# OUTPUT.net
KiCad netlist of a schematic drawn in Altium Designer
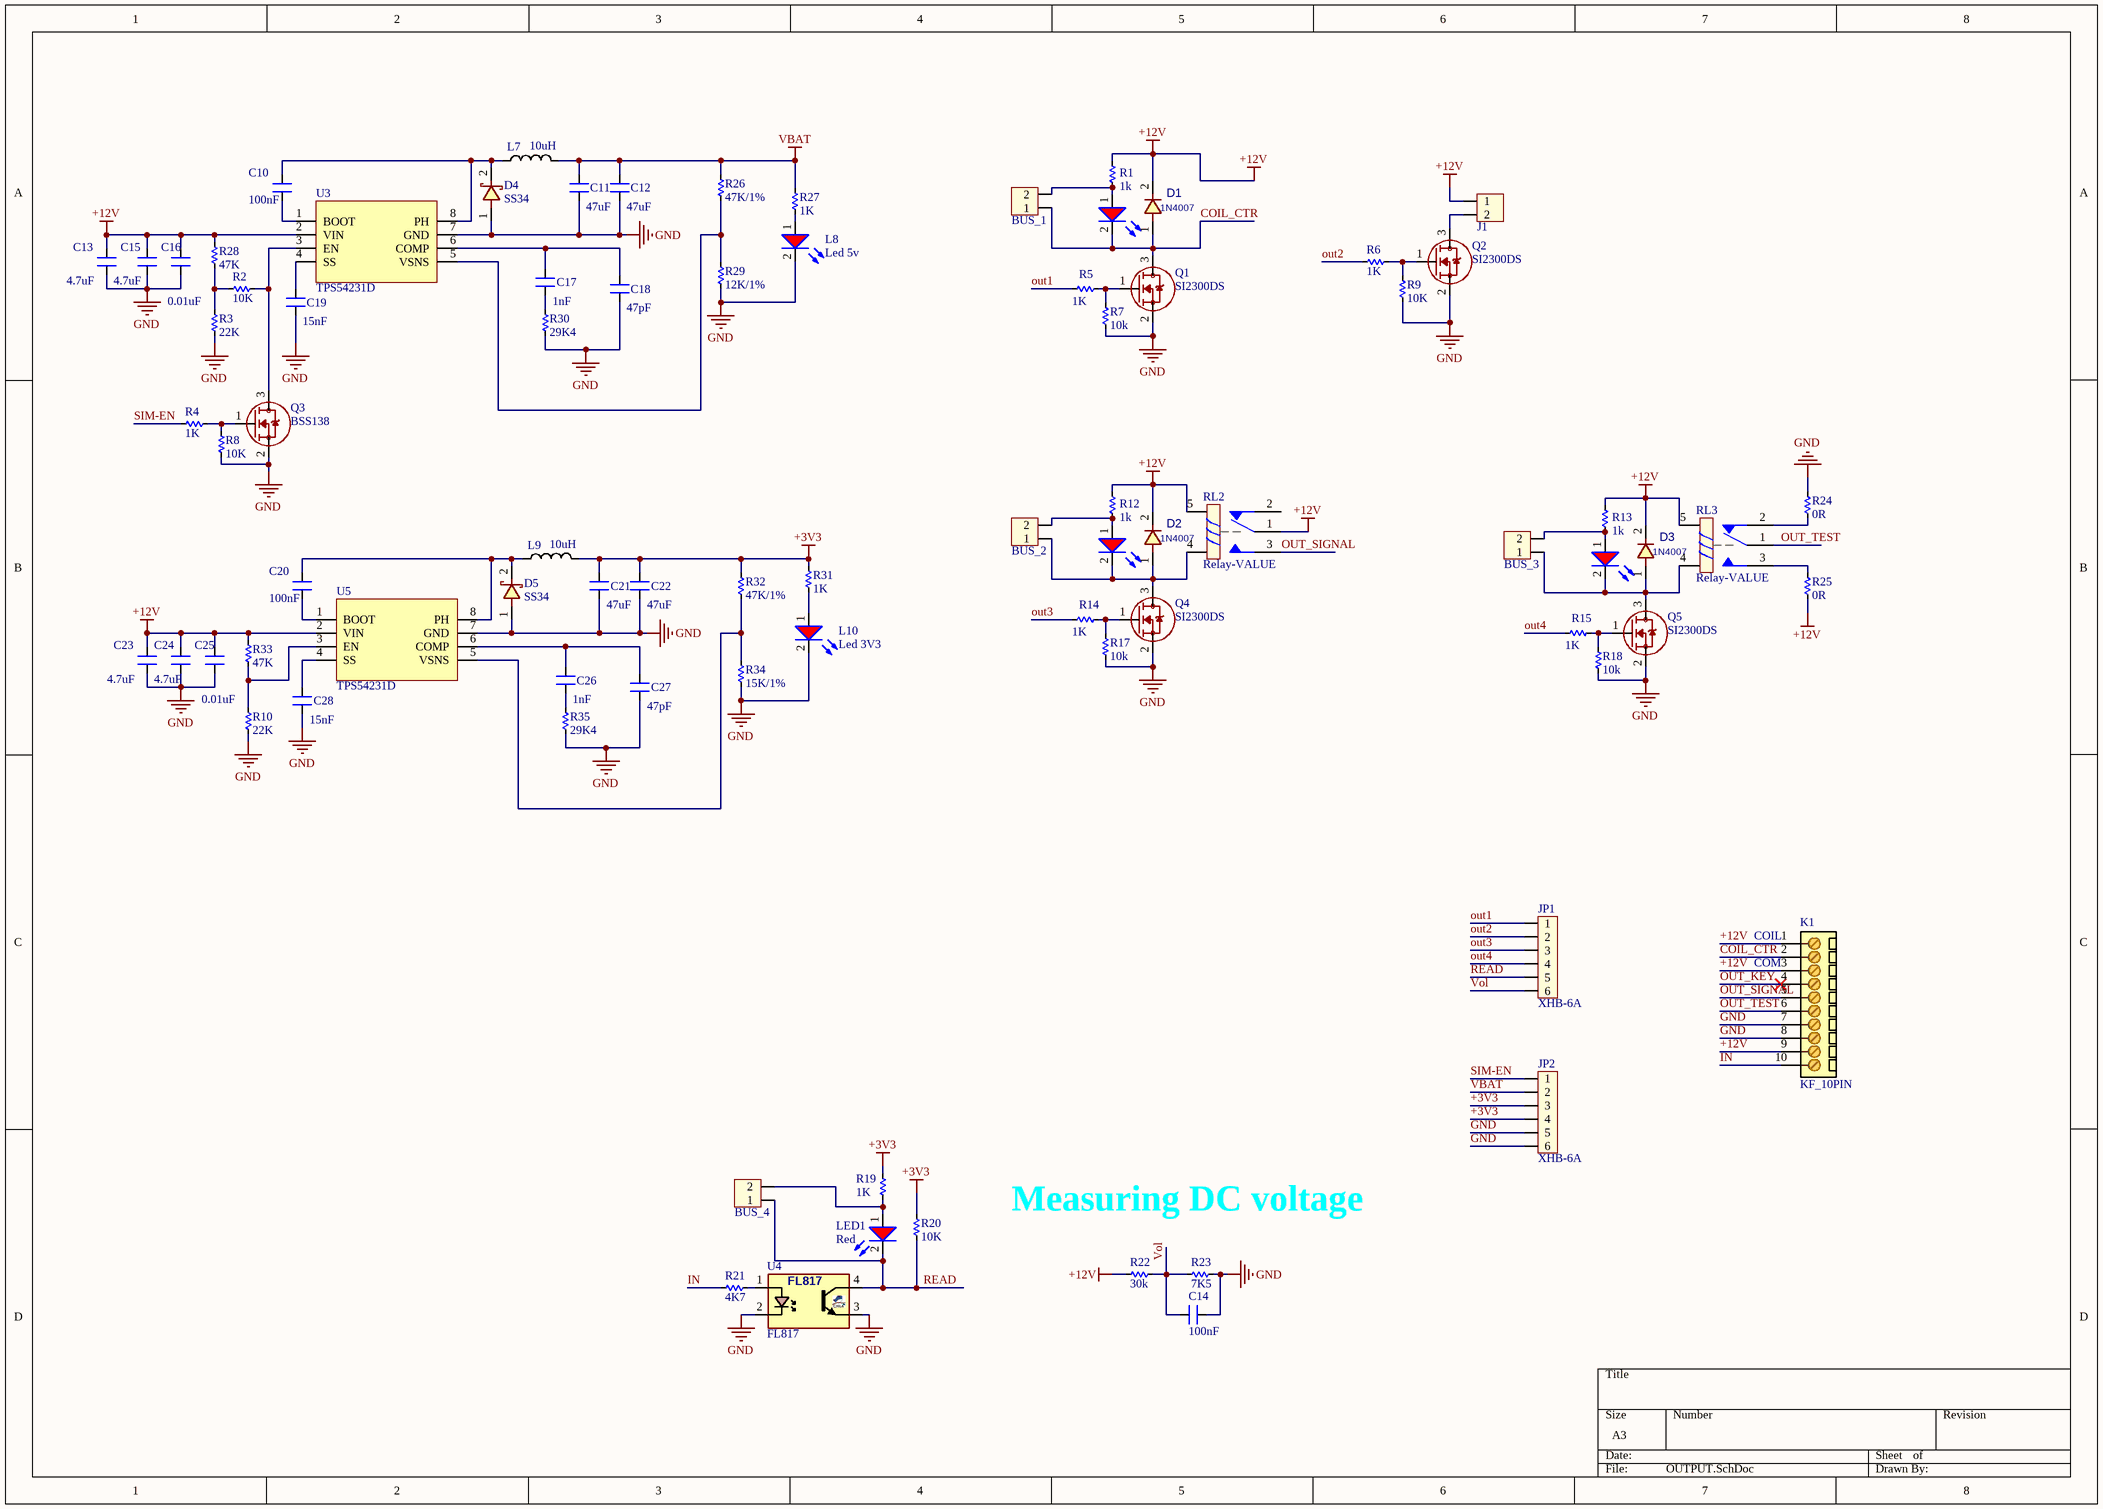
[diagram p0: OUTPUT.SchDoc]

(export (version "E")
  (design (tool "Eeschema 10.0.6"))
  (components
    (comp (ref "BUS_1")
      (value "BUS_2PIN")
      (footprint "CON2")
      (description "Connector 2")
      (libsource (lib "Tuấn Anh") (part "CON2"))
    )
    (comp (ref "BUS_2")
      (value "BUS_2PIN")
      (footprint "CON2")
      (description "Connector 2")
      (libsource (lib "Tuấn Anh") (part "CON2"))
    )
    (comp (ref "BUS_3")
      (value "BUS_2PIN")
      (footprint "CON2")
      (description "Connector 2")
      (libsource (lib "Tuấn Anh") (part "CON2"))
    )
    (comp (ref "BUS_4")
      (value "BUS_2PIN")
      (footprint "CON2")
      (description "Connector 2")
      (libsource (lib "Tuấn Anh") (part "CON2"))
    )
    (comp (ref "C10")
      (value "100nF")
      (footprint "CAP-0603")
      (description "Cap np W0.3")
      (fields (field (name "COPYRIGHT") "VanDungEvn"))
      (libsource (lib "tuananh_smd") (part "CAP CERAMIC"))
    )
    (comp (ref "C11")
      (value "47uF")
      (footprint "Cap-0805")
      (description "Cap np W0.3")
      (fields (field (name "COPYRIGHT") "VanDungEvn"))
      (libsource (lib "tuananh_smd") (part "CAP CERAMIC"))
    )
    (comp (ref "C12")
      (value "47uF")
      (footprint "Cap-0805")
      (description "Cap np W0.3")
      (fields (field (name "COPYRIGHT") "VanDungEvn"))
      (libsource (lib "tuananh_smd") (part "CAP CERAMIC"))
    )
    (comp (ref "C13")
      (value "4.7uF")
      (footprint "Cap-0805")
      (description "Cap np W0.3")
      (fields (field (name "COPYRIGHT") "VanDungEvn"))
      (libsource (lib "tuananh_smd") (part "CAP CERAMIC"))
    )
    (comp (ref "C14")
      (value "100nF")
      (footprint "CAP-0603")
      (description "Cap np W0.3")
      (fields (field (name "COPYRIGHT") "VanDungEvn"))
      (libsource (lib "tuananh_smd") (part "CAP CERAMIC"))
    )
    (comp (ref "C15")
      (value "4.7uF")
      (footprint "Cap-0805")
      (description "Cap np W0.3")
      (fields (field (name "COPYRIGHT") "VanDungEvn"))
      (libsource (lib "tuananh_smd") (part "CAP CERAMIC"))
    )
    (comp (ref "C16")
      (value "0.01uF")
      (footprint "CAP-0603")
      (description "Cap np W0.3")
      (fields (field (name "COPYRIGHT") "VanDungEvn"))
      (libsource (lib "tuananh_smd") (part "CAP CERAMIC"))
    )
    (comp (ref "C17")
      (value "1nF")
      (footprint "CAP-0603")
      (description "Cap np W0.3")
      (fields (field (name "COPYRIGHT") "VanDungEvn"))
      (libsource (lib "tuananh_smd") (part "CAP CERAMIC"))
    )
    (comp (ref "C18")
      (value "47pF")
      (footprint "CAP-0603")
      (description "Cap np W0.3")
      (fields (field (name "COPYRIGHT") "VanDungEvn"))
      (libsource (lib "tuananh_smd") (part "CAP CERAMIC"))
    )
    (comp (ref "C19")
      (value "15nF")
      (footprint "CAP-0603")
      (description "Cap np W0.3")
      (fields (field (name "COPYRIGHT") "VanDungEvn"))
      (libsource (lib "tuananh_smd") (part "CAP CERAMIC"))
    )
    (comp (ref "C20")
      (value "100nF")
      (footprint "CAP-0603")
      (description "Cap np W0.3")
      (fields (field (name "COPYRIGHT") "VanDungEvn"))
      (libsource (lib "tuananh_smd") (part "CAP CERAMIC"))
    )
    (comp (ref "C21")
      (value "47uF")
      (footprint "Cap-0805")
      (description "Cap np W0.3")
      (fields (field (name "COPYRIGHT") "VanDungEvn"))
      (libsource (lib "tuananh_smd") (part "CAP CERAMIC"))
    )
    (comp (ref "C22")
      (value "47uF")
      (footprint "Cap-0805")
      (description "Cap np W0.3")
      (fields (field (name "COPYRIGHT") "VanDungEvn"))
      (libsource (lib "tuananh_smd") (part "CAP CERAMIC"))
    )
    (comp (ref "C23")
      (value "4.7uF")
      (footprint "Cap-0805")
      (description "Cap np W0.3")
      (fields (field (name "COPYRIGHT") "VanDungEvn"))
      (libsource (lib "tuananh_smd") (part "CAP CERAMIC"))
    )
    (comp (ref "C24")
      (value "4.7uF")
      (footprint "Cap-0805")
      (description "Cap np W0.3")
      (fields (field (name "COPYRIGHT") "VanDungEvn"))
      (libsource (lib "tuananh_smd") (part "CAP CERAMIC"))
    )
    (comp (ref "C25")
      (value "0.01uF")
      (footprint "CAP-0603")
      (description "Cap np W0.3")
      (fields (field (name "COPYRIGHT") "VanDungEvn"))
      (libsource (lib "tuananh_smd") (part "CAP CERAMIC"))
    )
    (comp (ref "C26")
      (value "1nF")
      (footprint "CAP-0603")
      (description "Cap np W0.3")
      (fields (field (name "COPYRIGHT") "VanDungEvn"))
      (libsource (lib "tuananh_smd") (part "CAP CERAMIC"))
    )
    (comp (ref "C27")
      (value "47pF")
      (footprint "CAP-0603")
      (description "Cap np W0.3")
      (fields (field (name "COPYRIGHT") "VanDungEvn"))
      (libsource (lib "tuananh_smd") (part "CAP CERAMIC"))
    )
    (comp (ref "C28")
      (value "15nF")
      (footprint "CAP-0603")
      (description "Cap np W0.3")
      (fields (field (name "COPYRIGHT") "VanDungEvn"))
      (libsource (lib "tuananh_smd") (part "CAP CERAMIC"))
    )
    (comp (ref "D1")
      (value "1N4007")
      (footprint "SOD-323")
      (description "DIODE, GENERAL PURPOSE, 1000V/1A")
      (fields (field (name "MANF") "Diodes"))
      (libsource (lib "tuananh_smd") (part "1N4007"))
    )
    (comp (ref "D2")
      (value "1N4007")
      (footprint "SOD-323")
      (description "DIODE, GENERAL PURPOSE, 1000V/1A")
      (fields (field (name "MANF") "Diodes"))
      (libsource (lib "tuananh_smd") (part "1N4007"))
    )
    (comp (ref "D3")
      (value "1N4007")
      (footprint "SOD-323")
      (description "DIODE, GENERAL PURPOSE, 1000V/1A")
      (fields (field (name "MANF") "Diodes"))
      (libsource (lib "tuananh_smd") (part "1N4007"))
    )
    (comp (ref "D4") (value "SS34") (footprint "SS34") (libsource (lib "tuananh_smd") (part "DIODE_SCHOKY")))
    (comp (ref "D5") (value "SS34") (footprint "SS34") (libsource (lib "tuananh_smd") (part "DIODE_SCHOKY")))
    (comp (ref "J1")
      (value "BUS_2PIN")
      (footprint "CON2")
      (description "Connector 2")
      (libsource (lib "") (part "CON2_1"))
    )
    (comp (ref "JP1")
      (value "XHB-6A")
      (footprint "XH2.54-6P_THRU")
      (description "JP6 PIN")
      (libsource (lib "Tuấn Anh") (part "JP6"))
    )
    (comp (ref "JP2")
      (value "XHB-6A")
      (footprint "XH2.54-6P_THRU")
      (description "JP6 PIN")
      (libsource (lib "Tuấn Anh") (part "JP6"))
    )
    (comp (ref "K1")
      (value "KF_10PIN")
      (footprint "DOMINO-10PIN_3.5mm")
      (libsource (lib "Tuấn Anh") (part "KF_10PIN"))
    )
    (comp (ref "L2")
      (value "LED_R_1")
      (footprint "LED_0805_smd")
      (description "LED Red 3mm/5MM")
      (libsource (lib "Tuấn Anh") (part "LED_RED_3MM"))
    )
    (comp (ref "L4")
      (value "LED_R_1")
      (footprint "LED_0805_smd")
      (description "LED Red 3mm/5MM")
      (libsource (lib "Tuấn Anh") (part "LED_RED_3MM"))
    )
    (comp (ref "L5")
      (value "LED_R_1")
      (footprint "LED_0805_smd")
      (description "LED Red 3mm/5MM")
      (libsource (lib "Tuấn Anh") (part "LED_RED_3MM"))
    )
    (comp (ref "L7") (value "10uH") (footprint "INDUCTOR-06030") (libsource (lib "tuananh_smd") (part "IN")))
    (comp (ref "L8")
      (value "Led 5v")
      (footprint "LED_0805_smd")
      (fields (field (name "Comment") "LED"))
      (libsource (lib "tuananh_smd") (part "LED_RED_SMD"))
    )
    (comp (ref "L9") (value "10uH") (footprint "INDUCTOR-06030") (libsource (lib "tuananh_smd") (part "IN")))
    (comp (ref "L10")
      (value "Led 3V3")
      (footprint "LED_0805_smd")
      (fields (field (name "Comment") "LED"))
      (libsource (lib "tuananh_smd") (part "LED_RED_SMD"))
    )
    (comp (ref "LED1")
      (value "Red")
      (footprint "LED_0805_smd")
      (description "LED Red 3mm/5MM")
      (fields (field (name "Comment") "SMD"))
      (libsource (lib "tuananh_smd") (part "LED_RED_SMD"))
    )
    (comp (ref "Q1")
      (value "SI2300DS")
      (footprint "SOT-23")
      (description "MOSFET N-CH 3.6A 30V")
      (libsource (lib "tuananh_smd") (part "MOSFET_SI2300DS"))
    )
    (comp (ref "Q2")
      (value "SI2300DS")
      (footprint "SOT-23")
      (description "MOSFET N-CH 3.6A 30V")
      (libsource (lib "tuananh_smd") (part "MOSFET-N_SI2300DS"))
    )
    (comp (ref "Q3")
      (value "BSS138")
      (footprint "SOT-23")
      (description "MOSFET N-CH 0.2A-50V")
      (libsource (lib "tuananh_smd") (part "MOSFET-N_BSS138"))
    )
    (comp (ref "Q4")
      (value "SI2300DS")
      (footprint "SOT-23")
      (description "MOSFET N-CH 3.6A 30V")
      (libsource (lib "tuananh_smd") (part "MOSFET_SI2300DS"))
    )
    (comp (ref "Q5")
      (value "SI2300DS")
      (footprint "SOT-23")
      (description "MOSFET N-CH 3.6A 30V")
      (libsource (lib "tuananh_smd") (part "MOSFET_SI2300DS"))
    )
    (comp (ref "R1")
      (value "1k")
      (footprint "RES-0603")
      (description "Res")
      (fields
        (field (name "MANUFACTURER") "Generic Components")
        (field (name "PUBLISHER") "Altium Hobart Technology Centre")
      )
      (libsource (lib "Tuấn Anh") (part "Res"))
    )
    (comp (ref "R2")
      (value "10K")
      (footprint "RES-0603")
      (description "Res")
      (fields
        (field (name "MANUFACTURER") "Generic Components")
        (field (name "PUBLISHER") "Altium Hobart Technology Centre")
      )
      (libsource (lib "tuananh_smd") (part "Res"))
    )
    (comp (ref "R3")
      (value "22K")
      (footprint "RES-0603")
      (description "Res")
      (fields
        (field (name "MANUFACTURER") "Generic Components")
        (field (name "PUBLISHER") "Altium Hobart Technology Centre")
      )
      (libsource (lib "tuananh_smd") (part "Res"))
    )
    (comp (ref "R4")
      (value "1K")
      (footprint "RES-0603")
      (description "Res")
      (fields
        (field (name "MANUFACTURER") "Generic Components")
        (field (name "PUBLISHER") "Altium Hobart Technology Centre")
      )
      (libsource (lib "Tuấn Anh") (part "Res"))
    )
    (comp (ref "R5")
      (value "1K")
      (footprint "RES-0603")
      (description "Res")
      (fields
        (field (name "MANUFACTURER") "Generic Components")
        (field (name "PUBLISHER") "Altium Hobart Technology Centre")
      )
      (libsource (lib "Tuấn Anh") (part "Res"))
    )
    (comp (ref "R6")
      (value "1K")
      (footprint "RES-0603")
      (description "Res")
      (fields
        (field (name "MANUFACTURER") "Generic Components")
        (field (name "PUBLISHER") "Altium Hobart Technology Centre")
      )
      (libsource (lib "Tuấn Anh") (part "Res"))
    )
    (comp (ref "R7")
      (value "10k")
      (footprint "RES-0603")
      (description "Res")
      (fields
        (field (name "MANUFACTURER") "Generic Components")
        (field (name "PUBLISHER") "Altium Hobart Technology Centre")
      )
      (libsource (lib "Tuấn Anh") (part "Res"))
    )
    (comp (ref "R8")
      (value "10K")
      (footprint "RES-0603")
      (description "Res")
      (fields
        (field (name "MANUFACTURER") "Generic Components")
        (field (name "PUBLISHER") "Altium Hobart Technology Centre")
      )
      (libsource (lib "Tuấn Anh") (part "Res"))
    )
    (comp (ref "R9")
      (value "10K")
      (footprint "RES-0603")
      (description "Res")
      (fields
        (field (name "MANUFACTURER") "Generic Components")
        (field (name "PUBLISHER") "Altium Hobart Technology Centre")
      )
      (libsource (lib "Tuấn Anh") (part "Res"))
    )
    (comp (ref "R10")
      (value "22K")
      (footprint "RES-0603")
      (description "Res")
      (fields
        (field (name "MANUFACTURER") "Generic Components")
        (field (name "PUBLISHER") "Altium Hobart Technology Centre")
      )
      (libsource (lib "tuananh_smd") (part "Res"))
    )
    (comp (ref "R12")
      (value "1k")
      (footprint "RES-0603")
      (description "Res")
      (fields
        (field (name "MANUFACTURER") "Generic Components")
        (field (name "PUBLISHER") "Altium Hobart Technology Centre")
      )
      (libsource (lib "Tuấn Anh") (part "Res"))
    )
    (comp (ref "R13")
      (value "1k")
      (footprint "RES-0603")
      (description "Res")
      (fields
        (field (name "MANUFACTURER") "Generic Components")
        (field (name "PUBLISHER") "Altium Hobart Technology Centre")
      )
      (libsource (lib "Tuấn Anh") (part "Res"))
    )
    (comp (ref "R14")
      (value "1K")
      (footprint "RES-0603")
      (description "Res")
      (fields
        (field (name "MANUFACTURER") "Generic Components")
        (field (name "PUBLISHER") "Altium Hobart Technology Centre")
      )
      (libsource (lib "Tuấn Anh") (part "Res"))
    )
    (comp (ref "R15")
      (value "1K")
      (footprint "RES-0603")
      (description "Res")
      (fields
        (field (name "MANUFACTURER") "Generic Components")
        (field (name "PUBLISHER") "Altium Hobart Technology Centre")
      )
      (libsource (lib "Tuấn Anh") (part "Res"))
    )
    (comp (ref "R17")
      (value "10k")
      (footprint "RES-0603")
      (description "Res")
      (fields
        (field (name "MANUFACTURER") "Generic Components")
        (field (name "PUBLISHER") "Altium Hobart Technology Centre")
      )
      (libsource (lib "Tuấn Anh") (part "Res"))
    )
    (comp (ref "R18")
      (value "10k")
      (footprint "RES-0603")
      (description "Res")
      (fields
        (field (name "MANUFACTURER") "Generic Components")
        (field (name "PUBLISHER") "Altium Hobart Technology Centre")
      )
      (libsource (lib "Tuấn Anh") (part "Res"))
    )
    (comp (ref "R19")
      (value "1K")
      (footprint "RES-0603")
      (description "Res")
      (fields
        (field (name "MANUFACTURER") "Generic Components")
        (field (name "PUBLISHER") "Altium Hobart Technology Centre")
      )
      (libsource (lib "Tuấn Anh") (part "Res"))
    )
    (comp (ref "R20")
      (value "10K")
      (footprint "RES-0603")
      (description "Res")
      (fields
        (field (name "MANUFACTURER") "Generic Components")
        (field (name "PUBLISHER") "Altium Hobart Technology Centre")
      )
      (libsource (lib "Tuấn Anh") (part "Res"))
    )
    (comp (ref "R21")
      (value "4K7")
      (footprint "RES-0603")
      (description "Res")
      (fields
        (field (name "MANUFACTURER") "Generic Components")
        (field (name "PUBLISHER") "Altium Hobart Technology Centre")
      )
      (libsource (lib "Tuấn Anh") (part "Res"))
    )
    (comp (ref "R22")
      (value "30k")
      (footprint "RES-0603")
      (description "Res")
      (fields
        (field (name "MANUFACTURER") "Generic Components")
        (field (name "PUBLISHER") "Altium Hobart Technology Centre")
      )
      (libsource (lib "Tuấn Anh") (part "Res"))
    )
    (comp (ref "R23")
      (value "7K5")
      (footprint "RES-0603")
      (description "Res")
      (fields
        (field (name "MANUFACTURER") "Generic Components")
        (field (name "PUBLISHER") "Altium Hobart Technology Centre")
      )
      (libsource (lib "Tuấn Anh") (part "Res"))
    )
    (comp (ref "R24")
      (value "0R")
      (footprint "RES-1206")
      (description "Res")
      (fields
        (field (name "MANUFACTURER") "Generic Components")
        (field (name "PUBLISHER") "Altium Hobart Technology Centre")
      )
      (libsource (lib "Tuấn Anh") (part "Res"))
    )
    (comp (ref "R25")
      (value "0R")
      (footprint "RES-1206")
      (description "Res")
      (fields
        (field (name "MANUFACTURER") "Generic Components")
        (field (name "PUBLISHER") "Altium Hobart Technology Centre")
      )
      (libsource (lib "Tuấn Anh") (part "Res"))
    )
    (comp (ref "R26")
      (value "47K/1%")
      (footprint "RES-0603")
      (description "Res")
      (fields
        (field (name "MANUFACTURER") "Generic Components")
        (field (name "PUBLISHER") "Altium Hobart Technology Centre")
      )
      (libsource (lib "tuananh_smd") (part "Res"))
    )
    (comp (ref "R27")
      (value "1K")
      (footprint "RES-0603")
      (description "Res")
      (fields
        (field (name "MANUFACTURER") "Generic Components")
        (field (name "PUBLISHER") "Altium Hobart Technology Centre")
      )
      (libsource (lib "tuananh_smd") (part "Res"))
    )
    (comp (ref "R28")
      (value "47K")
      (footprint "RES-0603")
      (description "Res")
      (fields
        (field (name "MANUFACTURER") "Generic Components")
        (field (name "PUBLISHER") "Altium Hobart Technology Centre")
      )
      (libsource (lib "tuananh_smd") (part "Res"))
    )
    (comp (ref "R29")
      (value "12K/1%")
      (footprint "RES-0603")
      (description "Res")
      (fields
        (field (name "MANUFACTURER") "Generic Components")
        (field (name "PUBLISHER") "Altium Hobart Technology Centre")
      )
      (libsource (lib "tuananh_smd") (part "Res"))
    )
    (comp (ref "R30")
      (value "29K4")
      (footprint "RES-0603")
      (description "Res")
      (fields
        (field (name "MANUFACTURER") "Generic Components")
        (field (name "PUBLISHER") "Altium Hobart Technology Centre")
      )
      (libsource (lib "tuananh_smd") (part "Res"))
    )
    (comp (ref "R31")
      (value "1K")
      (footprint "RES-0603")
      (description "Res")
      (fields
        (field (name "MANUFACTURER") "Generic Components")
        (field (name "PUBLISHER") "Altium Hobart Technology Centre")
      )
      (libsource (lib "tuananh_smd") (part "Res"))
    )
    (comp (ref "R32")
      (value "47K/1%")
      (footprint "RES-0603")
      (description "Res")
      (fields
        (field (name "MANUFACTURER") "Generic Components")
        (field (name "PUBLISHER") "Altium Hobart Technology Centre")
      )
      (libsource (lib "tuananh_smd") (part "Res"))
    )
    (comp (ref "R33")
      (value "47K")
      (footprint "RES-0603")
      (description "Res")
      (fields
        (field (name "MANUFACTURER") "Generic Components")
        (field (name "PUBLISHER") "Altium Hobart Technology Centre")
      )
      (libsource (lib "tuananh_smd") (part "Res"))
    )
    (comp (ref "R34")
      (value "15K/1%")
      (footprint "RES-0603")
      (description "Res")
      (fields
        (field (name "MANUFACTURER") "Generic Components")
        (field (name "PUBLISHER") "Altium Hobart Technology Centre")
      )
      (libsource (lib "tuananh_smd") (part "Res"))
    )
    (comp (ref "R35")
      (value "29K4")
      (footprint "RES-0603")
      (description "Res")
      (fields
        (field (name "MANUFACTURER") "Generic Components")
        (field (name "PUBLISHER") "Altium Hobart Technology Centre")
      )
      (libsource (lib "tuananh_smd") (part "Res"))
    )
    (comp (ref "RL2")
      (value "Relay-VALUE")
      (footprint "RL-20A")
      (description "Relay SPDT")
      (libsource (lib "Tuấn Anh") (part "Relay-SONGLE"))
    )
    (comp (ref "RL3")
      (value "Relay-VALUE")
      (footprint "RL-20A")
      (description "Relay SPDT")
      (libsource (lib "Tuấn Anh") (part "Relay-SONGLE"))
    )
    (comp (ref "U3")
      (value "TPS54231D")
      (footprint "SOIC-8")
      (description "IC BUCK @TE")
      (libsource (lib "tuananh_smd") (part "TPS54231D"))
    )
    (comp (ref "U4")
      (value "FL817")
      (footprint "OPTO-PC817")
      (description "OPTOCOUPLER, TRANSISTOR, 4PIN")
      (libsource (lib "tuananh_smd") (part "OPTO-PC817"))
    )
    (comp (ref "U5")
      (value "TPS54231D")
      (footprint "SOIC-8")
      (description "IC BUCK @TE")
      (libsource (lib "tuananh_smd") (part "TPS54231D"))
    )
  )
  (nets
    (net (code "1") (name "+3V3") (class "Default")
      (node (ref "C21") (pin "2") (pinfunction "2_2") (pintype "passive"))
      (node (ref "C22") (pin "2") (pinfunction "2_2") (pintype "passive"))
      (node (ref "JP2") (pin "3") (pinfunction "3_3") (pintype "passive"))
      (node (ref "JP2") (pin "4") (pinfunction "4_4") (pintype "passive"))
      (node (ref "L9") (pin "2") (pinfunction "2_2") (pintype "passive"))
      (node (ref "R19") (pin "2") (pinfunction "2_2") (pintype "passive"))
      (node (ref "R20") (pin "1") (pinfunction "1_1") (pintype "passive"))
      (node (ref "R31") (pin "1") (pinfunction "1_1") (pintype "passive"))
      (node (ref "R32") (pin "1") (pinfunction "1_1") (pintype "passive"))
    )
    (net (code "2") (name "+12V") (class "Default")
      (node (ref "C13") (pin "2") (pinfunction "2_2") (pintype "passive"))
      (node (ref "C15") (pin "2") (pinfunction "2_2") (pintype "passive"))
      (node (ref "C16") (pin "2") (pinfunction "2_2") (pintype "passive"))
      (node (ref "C23") (pin "2") (pinfunction "2_2") (pintype "passive"))
      (node (ref "C24") (pin "2") (pinfunction "2_2") (pintype "passive"))
      (node (ref "C25") (pin "2") (pinfunction "2_2") (pintype "passive"))
      (node (ref "D1") (pin "2") (pinfunction "2_2") (pintype "passive"))
      (node (ref "D2") (pin "2") (pinfunction "2_2") (pintype "passive"))
      (node (ref "D3") (pin "2") (pinfunction "2_2") (pintype "passive"))
      (node (ref "J1") (pin "1") (pinfunction "1_1") (pintype "passive"))
      (node (ref "K1") (pin "1") (pinfunction "1_1") (pintype "passive"))
      (node (ref "K1") (pin "3") (pinfunction "3_3") (pintype "passive"))
      (node (ref "K1") (pin "9") (pinfunction "9_9") (pintype "passive"))
      (node (ref "R1") (pin "2") (pinfunction "2_2") (pintype "passive"))
      (node (ref "R12") (pin "2") (pinfunction "2_2") (pintype "passive"))
      (node (ref "R13") (pin "2") (pinfunction "2_2") (pintype "passive"))
      (node (ref "R22") (pin "2") (pinfunction "2_2") (pintype "passive"))
      (node (ref "R25") (pin "2") (pinfunction "2_2") (pintype "passive"))
      (node (ref "R28") (pin "1") (pinfunction "1_1") (pintype "passive"))
      (node (ref "R33") (pin "1") (pinfunction "1_1") (pintype "passive"))
      (node (ref "RL2") (pin "1") (pinfunction "1_1") (pintype "passive"))
      (node (ref "RL2") (pin "5") (pinfunction "5_5") (pintype "passive"))
      (node (ref "RL3") (pin "5") (pinfunction "5_5") (pintype "passive"))
      (node (ref "U3") (pin "2") (pinfunction "VIN_2") (pintype "passive"))
      (node (ref "U5") (pin "2") (pinfunction "VIN_2") (pintype "passive"))
    )
    (net (code "3") (name "/COIL_CTR") (class "Default")
      (node (ref "BUS_1") (pin "1") (pinfunction "1_1") (pintype "passive"))
      (node (ref "D1") (pin "1") (pinfunction "1_1") (pintype "passive"))
      (node (ref "K1") (pin "2") (pinfunction "2_2") (pintype "passive"))
      (node (ref "L2") (pin "2") (pinfunction "K_2") (pintype "passive"))
      (node (ref "Q1") (pin "3") (pinfunction "D_3") (pintype "passive"))
    )
    (net (code "4") (name "/IN") (class "Default")
      (node (ref "K1") (pin "10") (pinfunction "10_10") (pintype "passive"))
      (node (ref "R21") (pin "2") (pinfunction "2_2") (pintype "passive"))
    )
    (net (code "5") (name "/OUT_KEY") (class "Default")
      (node (ref "K1") (pin "4") (pinfunction "4_4") (pintype "passive+no_connect"))
    )
    (net (code "6") (name "/OUT_SIGNAL") (class "Default")
      (node (ref "K1") (pin "5") (pinfunction "5_5") (pintype "passive"))
      (node (ref "RL2") (pin "3") (pinfunction "3_3") (pintype "passive"))
    )
    (net (code "7") (name "/OUT_TEST") (class "Default")
      (node (ref "K1") (pin "6") (pinfunction "6_6") (pintype "passive"))
      (node (ref "RL3") (pin "1") (pinfunction "1_1") (pintype "passive"))
    )
    (net (code "8") (name "/READ") (class "Default")
      (node (ref "BUS_4") (pin "1") (pinfunction "1_1") (pintype "passive"))
      (node (ref "JP1") (pin "5") (pinfunction "5_5") (pintype "passive"))
      (node (ref "LED1") (pin "2") (pinfunction "K_2") (pintype "passive"))
      (node (ref "R20") (pin "2") (pinfunction "2_2") (pintype "passive"))
      (node (ref "U4") (pin "4") (pinfunction "C_4") (pintype "passive"))
    )
    (net (code "9") (name "/SIM-EN") (class "Default")
      (node (ref "JP2") (pin "1") (pinfunction "1_1") (pintype "passive"))
      (node (ref "R4") (pin "1") (pinfunction "1_1") (pintype "passive"))
    )
    (net (code "10") (name "/Vol") (class "Default")
      (node (ref "C14") (pin "2") (pinfunction "2_2") (pintype "passive"))
      (node (ref "JP1") (pin "6") (pinfunction "6_6") (pintype "passive"))
      (node (ref "R22") (pin "1") (pinfunction "1_1") (pintype "passive"))
      (node (ref "R23") (pin "2") (pinfunction "2_2") (pintype "passive"))
    )
    (net (code "11") (name "/out1") (class "Default")
      (node (ref "JP1") (pin "1") (pinfunction "1_1") (pintype "passive"))
      (node (ref "R5") (pin "2") (pinfunction "2_2") (pintype "passive"))
    )
    (net (code "12") (name "/out2") (class "Default")
      (node (ref "JP1") (pin "2") (pinfunction "2_2") (pintype "passive"))
      (node (ref "R6") (pin "2") (pinfunction "2_2") (pintype "passive"))
    )
    (net (code "13") (name "/out3") (class "Default")
      (node (ref "JP1") (pin "3") (pinfunction "3_3") (pintype "passive"))
      (node (ref "R14") (pin "2") (pinfunction "2_2") (pintype "passive"))
    )
    (net (code "14") (name "/out4") (class "Default")
      (node (ref "JP1") (pin "4") (pinfunction "4_4") (pintype "passive"))
      (node (ref "R15") (pin "2") (pinfunction "2_2") (pintype "passive"))
    )
    (net (code "15") (name "GND") (class "Default")
      (node (ref "C11") (pin "1") (pinfunction "1_1") (pintype "passive"))
      (node (ref "C12") (pin "1") (pinfunction "1_1") (pintype "passive"))
      (node (ref "C13") (pin "1") (pinfunction "1_1") (pintype "passive"))
      (node (ref "C14") (pin "1") (pinfunction "1_1") (pintype "passive"))
      (node (ref "C15") (pin "1") (pinfunction "1_1") (pintype "passive"))
      (node (ref "C16") (pin "1") (pinfunction "1_1") (pintype "passive"))
      (node (ref "C18") (pin "1") (pinfunction "1_1") (pintype "passive"))
      (node (ref "C19") (pin "1") (pinfunction "1_1") (pintype "passive"))
      (node (ref "C21") (pin "1") (pinfunction "1_1") (pintype "passive"))
      (node (ref "C22") (pin "1") (pinfunction "1_1") (pintype "passive"))
      (node (ref "C23") (pin "1") (pinfunction "1_1") (pintype "passive"))
      (node (ref "C24") (pin "1") (pinfunction "1_1") (pintype "passive"))
      (node (ref "C25") (pin "1") (pinfunction "1_1") (pintype "passive"))
      (node (ref "C27") (pin "1") (pinfunction "1_1") (pintype "passive"))
      (node (ref "C28") (pin "1") (pinfunction "1_1") (pintype "passive"))
      (node (ref "D4") (pin "1") (pinfunction "1_1") (pintype "passive"))
      (node (ref "D5") (pin "1") (pinfunction "1_1") (pintype "passive"))
      (node (ref "JP2") (pin "5") (pinfunction "5_5") (pintype "passive"))
      (node (ref "JP2") (pin "6") (pinfunction "6_6") (pintype "passive"))
      (node (ref "K1") (pin "7") (pinfunction "7_7") (pintype "passive"))
      (node (ref "K1") (pin "8") (pinfunction "8_8") (pintype "passive"))
      (node (ref "L10") (pin "2") (pinfunction "K_2") (pintype "passive"))
      (node (ref "L8") (pin "2") (pinfunction "K_2") (pintype "passive"))
      (node (ref "Q1") (pin "2") (pinfunction "S_2") (pintype "passive"))
      (node (ref "Q2") (pin "2") (pinfunction "S_2") (pintype "passive"))
      (node (ref "Q3") (pin "2") (pinfunction "S_2") (pintype "passive"))
      (node (ref "Q4") (pin "2") (pinfunction "S_2") (pintype "passive"))
      (node (ref "Q5") (pin "2") (pinfunction "S_2") (pintype "passive"))
      (node (ref "R10") (pin "2") (pinfunction "2_2") (pintype "passive"))
      (node (ref "R17") (pin "2") (pinfunction "2_2") (pintype "passive"))
      (node (ref "R18") (pin "2") (pinfunction "2_2") (pintype "passive"))
      (node (ref "R23") (pin "1") (pinfunction "1_1") (pintype "passive"))
      (node (ref "R24") (pin "1") (pinfunction "1_1") (pintype "passive"))
      (node (ref "R29") (pin "2") (pinfunction "2_2") (pintype "passive"))
      (node (ref "R3") (pin "2") (pinfunction "2_2") (pintype "passive"))
      (node (ref "R30") (pin "2") (pinfunction "2_2") (pintype "passive"))
      (node (ref "R34") (pin "2") (pinfunction "2_2") (pintype "passive"))
      (node (ref "R35") (pin "2") (pinfunction "2_2") (pintype "passive"))
      (node (ref "R7") (pin "2") (pinfunction "2_2") (pintype "passive"))
      (node (ref "R8") (pin "1") (pinfunction "1_1") (pintype "passive"))
      (node (ref "R9") (pin "2") (pinfunction "2_2") (pintype "passive"))
      (node (ref "U3") (pin "7") (pinfunction "GND_7") (pintype "passive"))
      (node (ref "U4") (pin "2") (pinfunction "K_2") (pintype "passive"))
      (node (ref "U4") (pin "3") (pinfunction "E_3") (pintype "passive"))
      (node (ref "U5") (pin "7") (pinfunction "GND_7") (pintype "passive"))
    )
    (net (code "16") (name "Net-(C17-Pad1)") (class "Default")
      (node (ref "C17") (pin "1") (pinfunction "1_1") (pintype "passive"))
      (node (ref "R30") (pin "1") (pinfunction "1_1") (pintype "passive"))
    )
    (net (code "17") (name "Net-(C26-Pad1)") (class "Default")
      (node (ref "C26") (pin "1") (pinfunction "1_1") (pintype "passive"))
      (node (ref "R35") (pin "1") (pinfunction "1_1") (pintype "passive"))
    )
    (net (code "18") (name "Net-(L2-A)") (class "Default")
      (node (ref "BUS_1") (pin "2") (pinfunction "2_2") (pintype "passive"))
      (node (ref "L2") (pin "1") (pinfunction "A_1") (pintype "passive"))
      (node (ref "R1") (pin "1") (pinfunction "1_1") (pintype "passive"))
    )
    (net (code "19") (name "Net-(L4-A)") (class "Default")
      (node (ref "BUS_2") (pin "2") (pinfunction "2_2") (pintype "passive"))
      (node (ref "L4") (pin "1") (pinfunction "A_1") (pintype "passive"))
      (node (ref "R12") (pin "1") (pinfunction "1_1") (pintype "passive"))
    )
    (net (code "20") (name "Net-(L4-K)") (class "Default")
      (node (ref "BUS_2") (pin "1") (pinfunction "1_1") (pintype "passive"))
      (node (ref "D2") (pin "1") (pinfunction "1_1") (pintype "passive"))
      (node (ref "L4") (pin "2") (pinfunction "K_2") (pintype "passive"))
      (node (ref "Q4") (pin "3") (pinfunction "D_3") (pintype "passive"))
      (node (ref "RL2") (pin "4") (pinfunction "4_4") (pintype "passive"))
    )
    (net (code "21") (name "Net-(L5-A)") (class "Default")
      (node (ref "BUS_3") (pin "2") (pinfunction "2_2") (pintype "passive"))
      (node (ref "L5") (pin "1") (pinfunction "A_1") (pintype "passive"))
      (node (ref "R13") (pin "1") (pinfunction "1_1") (pintype "passive"))
    )
    (net (code "22") (name "Net-(L5-K)") (class "Default")
      (node (ref "BUS_3") (pin "1") (pinfunction "1_1") (pintype "passive"))
      (node (ref "D3") (pin "1") (pinfunction "1_1") (pintype "passive"))
      (node (ref "L5") (pin "2") (pinfunction "K_2") (pintype "passive"))
      (node (ref "Q5") (pin "3") (pinfunction "D_3") (pintype "passive"))
      (node (ref "RL3") (pin "4") (pinfunction "4_4") (pintype "passive"))
    )
    (net (code "23") (name "Net-(L8-A)") (class "Default")
      (node (ref "L8") (pin "1") (pinfunction "A_1") (pintype "passive"))
      (node (ref "R27") (pin "2") (pinfunction "2_2") (pintype "passive"))
    )
    (net (code "24") (name "Net-(L10-A)") (class "Default")
      (node (ref "L10") (pin "1") (pinfunction "A_1") (pintype "passive"))
      (node (ref "R31") (pin "2") (pinfunction "2_2") (pintype "passive"))
    )
    (net (code "25") (name "Net-(LED1-A)") (class "Default")
      (node (ref "BUS_4") (pin "2") (pinfunction "2_2") (pintype "passive"))
      (node (ref "LED1") (pin "1") (pinfunction "A_1") (pintype "passive"))
      (node (ref "R19") (pin "1") (pinfunction "1_1") (pintype "passive"))
    )
    (net (code "26") (name "Net-(Q1-G)") (class "Default")
      (node (ref "Q1") (pin "1") (pinfunction "G_1") (pintype "passive"))
      (node (ref "R5") (pin "1") (pinfunction "1_1") (pintype "passive"))
      (node (ref "R7") (pin "1") (pinfunction "1_1") (pintype "passive"))
    )
    (net (code "27") (name "Net-(Q2-D)") (class "Default")
      (node (ref "J1") (pin "2") (pinfunction "2_2") (pintype "passive"))
      (node (ref "Q2") (pin "3") (pinfunction "D_3") (pintype "passive"))
    )
    (net (code "28") (name "Net-(Q2-G)") (class "Default")
      (node (ref "Q2") (pin "1") (pinfunction "G_1") (pintype "passive"))
      (node (ref "R6") (pin "1") (pinfunction "1_1") (pintype "passive"))
      (node (ref "R9") (pin "1") (pinfunction "1_1") (pintype "passive"))
    )
    (net (code "29") (name "Net-(Q3-D)") (class "Default")
      (node (ref "Q3") (pin "3") (pinfunction "D_3") (pintype "passive"))
      (node (ref "R2") (pin "2") (pinfunction "2_2") (pintype "passive"))
      (node (ref "U3") (pin "3") (pinfunction "EN_3") (pintype "passive"))
    )
    (net (code "30") (name "Net-(Q3-G)") (class "Default")
      (node (ref "Q3") (pin "1") (pinfunction "G_1") (pintype "passive"))
      (node (ref "R4") (pin "2") (pinfunction "2_2") (pintype "passive"))
      (node (ref "R8") (pin "2") (pinfunction "2_2") (pintype "passive"))
    )
    (net (code "31") (name "Net-(Q4-G)") (class "Default")
      (node (ref "Q4") (pin "1") (pinfunction "G_1") (pintype "passive"))
      (node (ref "R14") (pin "1") (pinfunction "1_1") (pintype "passive"))
      (node (ref "R17") (pin "1") (pinfunction "1_1") (pintype "passive"))
    )
    (net (code "32") (name "Net-(Q5-G)") (class "Default")
      (node (ref "Q5") (pin "1") (pinfunction "G_1") (pintype "passive"))
      (node (ref "R15") (pin "1") (pinfunction "1_1") (pintype "passive"))
      (node (ref "R18") (pin "1") (pinfunction "1_1") (pintype "passive"))
    )
    (net (code "33") (name "Net-(R2-Pad1)") (class "Default")
      (node (ref "R2") (pin "1") (pinfunction "1_1") (pintype "passive"))
      (node (ref "R28") (pin "2") (pinfunction "2_2") (pintype "passive"))
      (node (ref "R3") (pin "1") (pinfunction "1_1") (pintype "passive"))
    )
    (net (code "34") (name "Net-(R24-Pad2)") (class "Default")
      (node (ref "R24") (pin "2") (pinfunction "2_2") (pintype "passive"))
      (node (ref "RL3") (pin "2") (pinfunction "2_2") (pintype "passive"))
    )
    (net (code "35") (name "Net-(R25-Pad1)") (class "Default")
      (node (ref "R25") (pin "1") (pinfunction "1_1") (pintype "passive"))
      (node (ref "RL3") (pin "3") (pinfunction "3_3") (pintype "passive"))
    )
    (net (code "36") (name "Net-(U3-BOOT)") (class "Default")
      (node (ref "C10") (pin "1") (pinfunction "1_1") (pintype "passive"))
      (node (ref "U3") (pin "1") (pinfunction "BOOT_1") (pintype "passive"))
    )
    (net (code "37") (name "Net-(U3-COMP)") (class "Default")
      (node (ref "C17") (pin "2") (pinfunction "2_2") (pintype "passive"))
      (node (ref "C18") (pin "2") (pinfunction "2_2") (pintype "passive"))
      (node (ref "U3") (pin "6") (pinfunction "COMP_6") (pintype "passive"))
    )
    (net (code "38") (name "Net-(U3-PH)") (class "Default")
      (node (ref "C10") (pin "2") (pinfunction "2_2") (pintype "passive"))
      (node (ref "D4") (pin "2") (pinfunction "2_2") (pintype "passive"))
      (node (ref "L7") (pin "1") (pinfunction "1_1") (pintype "passive"))
      (node (ref "U3") (pin "8") (pinfunction "PH_8") (pintype "passive"))
    )
    (net (code "39") (name "Net-(U3-SS)") (class "Default")
      (node (ref "C19") (pin "2") (pinfunction "2_2") (pintype "passive"))
      (node (ref "U3") (pin "4") (pinfunction "SS_4") (pintype "passive"))
    )
    (net (code "40") (name "Net-(U3-VSNS)") (class "Default")
      (node (ref "R26") (pin "2") (pinfunction "2_2") (pintype "passive"))
      (node (ref "R29") (pin "1") (pinfunction "1_1") (pintype "passive"))
      (node (ref "U3") (pin "5") (pinfunction "VSNS_5") (pintype "passive"))
    )
    (net (code "41") (name "Net-(U4-A)") (class "Default")
      (node (ref "R21") (pin "1") (pinfunction "1_1") (pintype "passive"))
      (node (ref "U4") (pin "1") (pinfunction "A_1") (pintype "passive"))
    )
    (net (code "42") (name "Net-(U5-BOOT)") (class "Default")
      (node (ref "C20") (pin "1") (pinfunction "1_1") (pintype "passive"))
      (node (ref "U5") (pin "1") (pinfunction "BOOT_1") (pintype "passive"))
    )
    (net (code "43") (name "Net-(U5-COMP)") (class "Default")
      (node (ref "C26") (pin "2") (pinfunction "2_2") (pintype "passive"))
      (node (ref "C27") (pin "2") (pinfunction "2_2") (pintype "passive"))
      (node (ref "U5") (pin "6") (pinfunction "COMP_6") (pintype "passive"))
    )
    (net (code "44") (name "Net-(U5-EN)") (class "Default")
      (node (ref "R10") (pin "1") (pinfunction "1_1") (pintype "passive"))
      (node (ref "R33") (pin "2") (pinfunction "2_2") (pintype "passive"))
      (node (ref "U5") (pin "3") (pinfunction "EN_3") (pintype "passive"))
    )
    (net (code "45") (name "Net-(U5-PH)") (class "Default")
      (node (ref "C20") (pin "2") (pinfunction "2_2") (pintype "passive"))
      (node (ref "D5") (pin "2") (pinfunction "2_2") (pintype "passive"))
      (node (ref "L9") (pin "1") (pinfunction "1_1") (pintype "passive"))
      (node (ref "U5") (pin "8") (pinfunction "PH_8") (pintype "passive"))
    )
    (net (code "46") (name "Net-(U5-SS)") (class "Default")
      (node (ref "C28") (pin "2") (pinfunction "2_2") (pintype "passive"))
      (node (ref "U5") (pin "4") (pinfunction "SS_4") (pintype "passive"))
    )
    (net (code "47") (name "Net-(U5-VSNS)") (class "Default")
      (node (ref "R32") (pin "2") (pinfunction "2_2") (pintype "passive"))
      (node (ref "R34") (pin "1") (pinfunction "1_1") (pintype "passive"))
      (node (ref "U5") (pin "5") (pinfunction "VSNS_5") (pintype "passive"))
    )
    (net (code "48") (name "VBAT") (class "Default")
      (node (ref "C11") (pin "2") (pinfunction "2_2") (pintype "passive"))
      (node (ref "C12") (pin "2") (pinfunction "2_2") (pintype "passive"))
      (node (ref "JP2") (pin "2") (pinfunction "2_2") (pintype "passive"))
      (node (ref "L7") (pin "2") (pinfunction "2_2") (pintype "passive"))
      (node (ref "R26") (pin "1") (pinfunction "1_1") (pintype "passive"))
      (node (ref "R27") (pin "1") (pinfunction "1_1") (pintype "passive"))
    )
    (net (code "49") (name "unconnected-(RL2-Pad2)") (class "Default")
      (node (ref "RL2") (pin "2") (pinfunction "2_2") (pintype "passive"))
    )
  )
)
